# P5d_Filter2B.net
KiCad netlist of a schematic drawn in Altium Designer
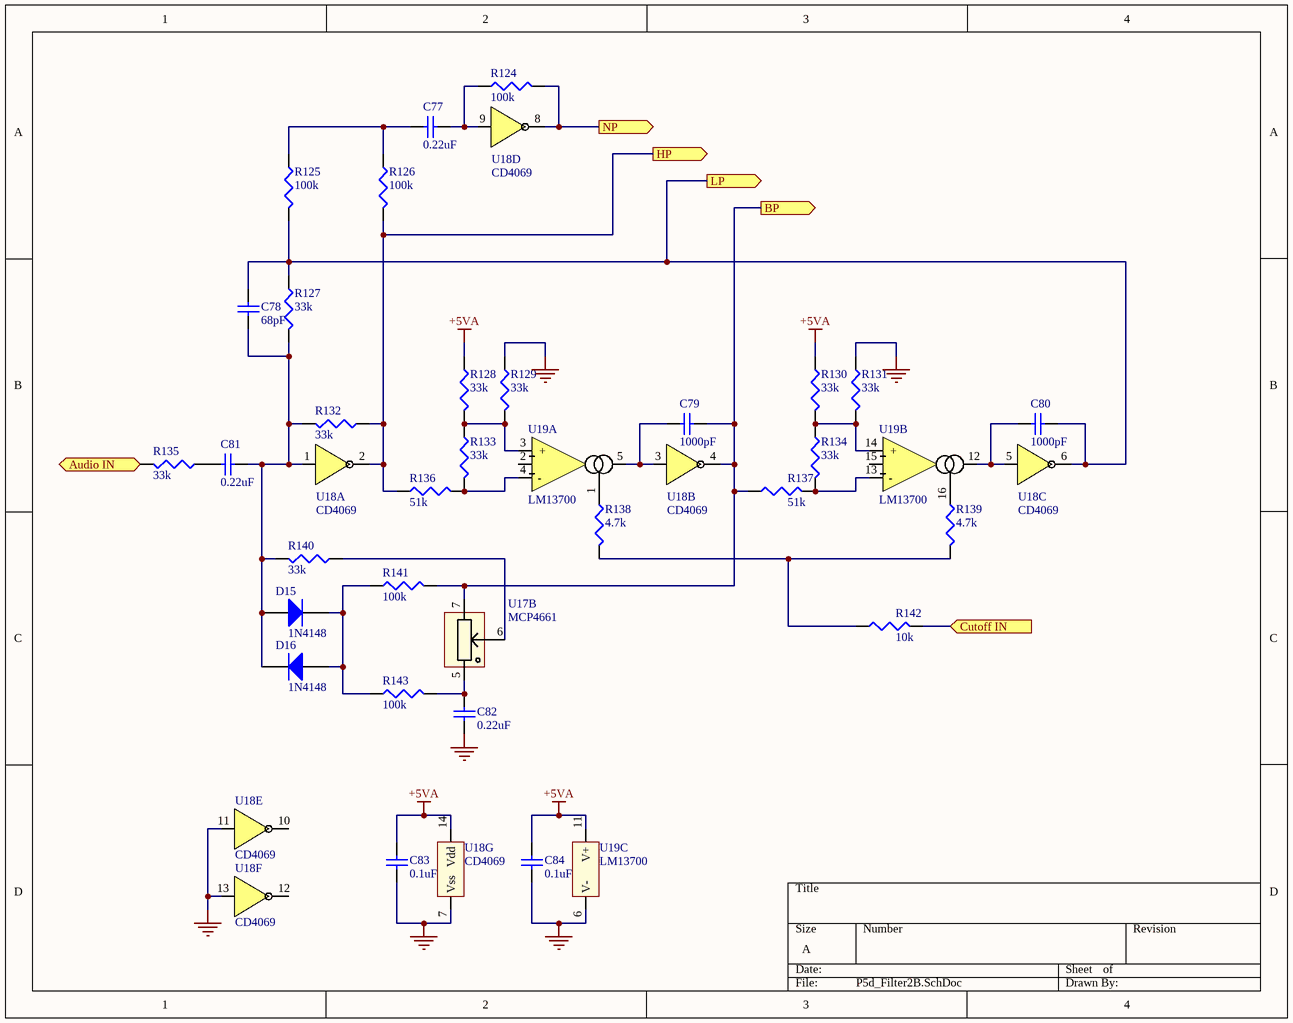
[diagram p0: P5d_Filter2B.SchDoc]

(export (version "E")
  (design (tool "Eeschema 10.0.6"))
  (components
    (comp (ref "C77")
      (value "0.22uF")
      (footprint "CAP 0603 (1608 metric)")
      (description "Capacitor (Semiconductor SIM Model)")
      (libsource (lib "Miscellaneous Devices") (part "Cap Semi"))
    )
    (comp (ref "C78")
      (value "68pF")
      (footprint "CAP 0603 (1608 metric)")
      (description "Capacitor (Semiconductor SIM Model)")
      (libsource (lib "Miscellaneous Devices") (part "Cap Semi"))
    )
    (comp (ref "C79")
      (value "1000pF")
      (footprint "CAP 0603 (1608 metric)")
      (description "Capacitor (Semiconductor SIM Model)")
      (libsource (lib "Miscellaneous Devices") (part "Cap Semi"))
    )
    (comp (ref "C80")
      (value "1000pF")
      (footprint "CAP 0603 (1608 metric)")
      (description "Capacitor (Semiconductor SIM Model)")
      (libsource (lib "Miscellaneous Devices") (part "Cap Semi"))
    )
    (comp (ref "C81")
      (value "0.22uF")
      (footprint "CAP 0603 (1608 metric)")
      (description "Capacitor (Semiconductor SIM Model)")
      (libsource (lib "Miscellaneous Devices") (part "Cap Semi"))
    )
    (comp (ref "C82")
      (value "0.22uF")
      (footprint "CAP 0603 (1608 metric)")
      (description "Capacitor (Semiconductor SIM Model)")
      (libsource (lib "Miscellaneous Devices") (part "Cap Semi"))
    )
    (comp (ref "C83")
      (value "0.1uF")
      (footprint "CAP 0603 (1608 metric)")
      (description "Capacitor (Semiconductor SIM Model)")
      (libsource (lib "Miscellaneous Devices") (part "Cap Semi"))
    )
    (comp (ref "C84")
      (value "0.1uF")
      (footprint "CAP 0603 (1608 metric)")
      (description "Capacitor (Semiconductor SIM Model)")
      (libsource (lib "Miscellaneous Devices") (part "Cap Semi"))
    )
    (comp (ref "D15")
      (value "1N4148")
      (description "High Conductance Fast Diode")
      (libsource (lib "Miscellaneous Devices") (part "Diode 1N4148"))
    )
    (comp (ref "D16")
      (value "1N4148")
      (description "High Conductance Fast Diode")
      (libsource (lib "Miscellaneous Devices") (part "Diode 1N4148"))
    )
    (comp (ref "R124")
      (value "100k")
      (footprint "RES 0603 (1608 metric)")
      (description "Resistor")
      (libsource (lib "Miscellaneous Devices") (part "Res3"))
    )
    (comp (ref "R125")
      (value "100k")
      (footprint "RES 0603 (1608 metric)")
      (description "Resistor")
      (libsource (lib "Miscellaneous Devices") (part "Res3"))
    )
    (comp (ref "R126")
      (value "100k")
      (footprint "RES 0603 (1608 metric)")
      (description "Resistor")
      (libsource (lib "Miscellaneous Devices") (part "Res3"))
    )
    (comp (ref "R127")
      (value "33k")
      (footprint "RES 0603 (1608 metric)")
      (description "Resistor")
      (libsource (lib "Miscellaneous Devices") (part "Res3"))
    )
    (comp (ref "R128")
      (value "33k")
      (footprint "RES 0603 (1608 metric)")
      (description "Resistor")
      (libsource (lib "Miscellaneous Devices") (part "Res3"))
    )
    (comp (ref "R129")
      (value "33k")
      (footprint "RES 0603 (1608 metric)")
      (description "Resistor")
      (libsource (lib "Miscellaneous Devices") (part "Res3"))
    )
    (comp (ref "R130")
      (value "33k")
      (footprint "RES 0603 (1608 metric)")
      (description "Resistor")
      (libsource (lib "Miscellaneous Devices") (part "Res3"))
    )
    (comp (ref "R131")
      (value "33k")
      (footprint "RES 0603 (1608 metric)")
      (description "Resistor")
      (libsource (lib "Miscellaneous Devices") (part "Res3"))
    )
    (comp (ref "R132")
      (value "33k")
      (footprint "RES 0603 (1608 metric)")
      (description "Resistor")
      (libsource (lib "Miscellaneous Devices") (part "Res3"))
    )
    (comp (ref "R133")
      (value "33k")
      (footprint "RES 0603 (1608 metric)")
      (description "Resistor")
      (libsource (lib "Miscellaneous Devices") (part "Res3"))
    )
    (comp (ref "R134")
      (value "33k")
      (footprint "RES 0603 (1608 metric)")
      (description "Resistor")
      (libsource (lib "Miscellaneous Devices") (part "Res3"))
    )
    (comp (ref "R135")
      (value "33k")
      (footprint "RES 0603 (1608 metric)")
      (description "Resistor")
      (libsource (lib "Miscellaneous Devices") (part "Res3"))
    )
    (comp (ref "R136")
      (value "51k")
      (footprint "RES 0603 (1608 metric)")
      (description "Resistor")
      (libsource (lib "Miscellaneous Devices") (part "Res3"))
    )
    (comp (ref "R137")
      (value "51k")
      (footprint "RES 0603 (1608 metric)")
      (description "Resistor")
      (libsource (lib "Miscellaneous Devices") (part "Res3"))
    )
    (comp (ref "R138")
      (value "4.7k")
      (footprint "RES 0603 (1608 metric)")
      (description "Resistor")
      (libsource (lib "Miscellaneous Devices") (part "Res3"))
    )
    (comp (ref "R139")
      (value "4.7k")
      (footprint "RES 0603 (1608 metric)")
      (description "Resistor")
      (libsource (lib "Miscellaneous Devices") (part "Res3"))
    )
    (comp (ref "R140")
      (value "33k")
      (footprint "RES 0603 (1608 metric)")
      (description "Resistor")
      (libsource (lib "Miscellaneous Devices") (part "Res3"))
    )
    (comp (ref "R141")
      (value "100k")
      (footprint "RES 0603 (1608 metric)")
      (description "Resistor")
      (libsource (lib "Miscellaneous Devices") (part "Res3"))
    )
    (comp (ref "R142")
      (value "10k")
      (footprint "RES 0603 (1608 metric)")
      (description "Resistor")
      (libsource (lib "Miscellaneous Devices") (part "Res3"))
    )
    (comp (ref "R143")
      (value "100k")
      (footprint "RES 0603 (1608 metric)")
      (description "Resistor")
      (libsource (lib "Miscellaneous Devices") (part "Res3"))
    )
    (comp (ref "U17")
      (value "MCP4661")
      (description "Dual DigiPot non volatile I2C")
      (libsource (lib "FilterPoC") (part "MCP4661"))
    )
    (comp (ref "U18")
      (value "CD4069")
      (description "Hex Inverter")
      (libsource (lib "FilterPoC") (part "CD4069"))
    )
    (comp (ref "U19")
      (value "LM13700")
      (description "Dual Transconductance OpAmp")
      (libsource (lib "") (part "LM13700M_1"))
    )
  )
  (nets
    (net (code "1") (name "+5VA") (class "Default")
      (node (ref "C83") (pin "1") (pinfunction "1_1") (pintype "passive"))
      (node (ref "C84") (pin "1") (pinfunction "1_1") (pintype "passive"))
      (node (ref "R128") (pin "1") (pinfunction "1_1") (pintype "passive"))
      (node (ref "R130") (pin "1") (pinfunction "1_1") (pintype "passive"))
      (node (ref "U18") (pin "14") (pinfunction "Vdd_14") (pintype "power_in"))
      (node (ref "U19") (pin "11") (pinfunction "V+_11") (pintype "power_in"))
    )
    (net (code "2") (name "/Audio IN") (class "Default")
      (node (ref "R135") (pin "2") (pinfunction "2_2") (pintype "passive"))
    )
    (net (code "3") (name "/BP") (class "Default")
      (node (ref "C79") (pin "2") (pinfunction "2_2") (pintype "passive"))
      (node (ref "R137") (pin "1") (pinfunction "1_1") (pintype "passive"))
      (node (ref "R141") (pin "2") (pinfunction "2_2") (pintype "passive"))
      (node (ref "U17") (pin "7") (pinfunction "P1A_7") (pintype "passive"))
      (node (ref "U18") (pin "4") (pinfunction "~{B}_4") (pintype "passive"))
    )
    (net (code "4") (name "/Cutoff IN") (class "Default")
      (node (ref "R142") (pin "2") (pinfunction "2_2") (pintype "passive"))
    )
    (net (code "5") (name "/HP") (class "Default")
      (node (ref "R126") (pin "2") (pinfunction "2_2") (pintype "passive"))
      (node (ref "R132") (pin "1") (pinfunction "1_1") (pintype "passive"))
      (node (ref "R136") (pin "1") (pinfunction "1_1") (pintype "passive"))
      (node (ref "U18") (pin "2") (pinfunction "~{A}_2") (pintype "passive"))
    )
    (net (code "6") (name "/LP") (class "Default")
      (node (ref "C78") (pin "2") (pinfunction "2_2") (pintype "passive"))
      (node (ref "C80") (pin "2") (pinfunction "2_2") (pintype "passive"))
      (node (ref "R125") (pin "2") (pinfunction "2_2") (pintype "passive"))
      (node (ref "R127") (pin "1") (pinfunction "1_1") (pintype "passive"))
      (node (ref "U18") (pin "6") (pinfunction "~{C}_6") (pintype "passive"))
    )
    (net (code "7") (name "/NP") (class "Default")
      (node (ref "R124") (pin "2") (pinfunction "2_2") (pintype "passive"))
      (node (ref "U18") (pin "8") (pinfunction "~{D}_8") (pintype "passive"))
    )
    (net (code "8") (name "GND") (class "Default")
      (node (ref "C82") (pin "2") (pinfunction "2_2") (pintype "passive"))
      (node (ref "C83") (pin "2") (pinfunction "2_2") (pintype "passive"))
      (node (ref "C84") (pin "2") (pinfunction "2_2") (pintype "passive"))
      (node (ref "R129") (pin "1") (pinfunction "1_1") (pintype "passive"))
      (node (ref "R131") (pin "1") (pinfunction "1_1") (pintype "passive"))
      (node (ref "U18") (pin "11") (pinfunction "E_11") (pintype "passive"))
      (node (ref "U18") (pin "13") (pinfunction "F_13") (pintype "passive"))
      (node (ref "U18") (pin "7") (pinfunction "Vss_7") (pintype "power_in"))
      (node (ref "U19") (pin "6") (pinfunction "V-_6") (pintype "power_in"))
    )
    (net (code "9") (name "Net-(C77-Pad1)") (class "Default")
      (node (ref "C77") (pin "1") (pinfunction "1_1") (pintype "passive"))
      (node (ref "R125") (pin "1") (pinfunction "1_1") (pintype "passive"))
      (node (ref "R126") (pin "1") (pinfunction "1_1") (pintype "passive"))
    )
    (net (code "10") (name "Net-(C81-Pad1)") (class "Default")
      (node (ref "C81") (pin "1") (pinfunction "1_1") (pintype "passive"))
      (node (ref "R135") (pin "1") (pinfunction "1_1") (pintype "passive"))
    )
    (net (code "11") (name "Net-(D15-A)") (class "Default")
      (node (ref "C78") (pin "1") (pinfunction "1_1") (pintype "passive"))
      (node (ref "C81") (pin "2") (pinfunction "2_2") (pintype "passive"))
      (node (ref "D15") (pin "1") (pinfunction "A_1") (pintype "passive"))
      (node (ref "D16") (pin "2") (pinfunction "K_2") (pintype "passive"))
      (node (ref "R127") (pin "2") (pinfunction "2_2") (pintype "passive"))
      (node (ref "R132") (pin "2") (pinfunction "2_2") (pintype "passive"))
      (node (ref "R140") (pin "2") (pinfunction "2_2") (pintype "passive"))
      (node (ref "U18") (pin "1") (pinfunction "A_1") (pintype "passive"))
    )
    (net (code "12") (name "Net-(D15-K)") (class "Default")
      (node (ref "D15") (pin "2") (pinfunction "K_2") (pintype "passive"))
      (node (ref "D16") (pin "1") (pinfunction "A_1") (pintype "passive"))
      (node (ref "R141") (pin "1") (pinfunction "1_1") (pintype "passive"))
      (node (ref "R143") (pin "1") (pinfunction "1_1") (pintype "passive"))
    )
    (net (code "13") (name "Net-(R138-Pad2)") (class "Default")
      (node (ref "R138") (pin "2") (pinfunction "2_2") (pintype "passive"))
      (node (ref "R139") (pin "2") (pinfunction "2_2") (pintype "passive"))
      (node (ref "R142") (pin "1") (pinfunction "1_1") (pintype "passive"))
    )
    (net (code "14") (name "Net-(U17B-P1B)") (class "Default")
      (node (ref "C82") (pin "1") (pinfunction "1_1") (pintype "passive"))
      (node (ref "R143") (pin "2") (pinfunction "2_2") (pintype "passive"))
      (node (ref "U17") (pin "5") (pinfunction "P1B_5") (pintype "passive"))
    )
    (net (code "15") (name "Net-(U17B-P1W)") (class "Default")
      (node (ref "R140") (pin "1") (pinfunction "1_1") (pintype "passive"))
      (node (ref "U17") (pin "6") (pinfunction "P1W_6") (pintype "passive"))
    )
    (net (code "16") (name "Net-(U18B-B)") (class "Default")
      (node (ref "C79") (pin "1") (pinfunction "1_1") (pintype "passive"))
      (node (ref "U18") (pin "3") (pinfunction "B_3") (pintype "passive"))
      (node (ref "U19") (pin "5") (pinfunction "OUT_5") (pintype "passive"))
    )
    (net (code "17") (name "Net-(U18C-C)") (class "Default")
      (node (ref "C80") (pin "1") (pinfunction "1_1") (pintype "passive"))
      (node (ref "U18") (pin "5") (pinfunction "C_5") (pintype "passive"))
      (node (ref "U19") (pin "12") (pinfunction "OUT_12") (pintype "passive"))
    )
    (net (code "18") (name "Net-(U18D-D)") (class "Default")
      (node (ref "C77") (pin "2") (pinfunction "2_2") (pintype "passive"))
      (node (ref "R124") (pin "1") (pinfunction "1_1") (pintype "passive"))
      (node (ref "U18") (pin "9") (pinfunction "D_9") (pintype "passive"))
    )
    (net (code "19") (name "Net-(U19A-+)") (class "Default")
      (node (ref "R128") (pin "2") (pinfunction "2_2") (pintype "passive"))
      (node (ref "R129") (pin "2") (pinfunction "2_2") (pintype "passive"))
      (node (ref "R133") (pin "1") (pinfunction "1_1") (pintype "passive"))
      (node (ref "U19") (pin "3") (pinfunction "+_3") (pintype "passive"))
    )
    (net (code "20") (name "Net-(U19A--)") (class "Default")
      (node (ref "R133") (pin "2") (pinfunction "2_2") (pintype "passive"))
      (node (ref "R136") (pin "2") (pinfunction "2_2") (pintype "passive"))
      (node (ref "U19") (pin "4") (pinfunction "-_4") (pintype "passive"))
    )
    (net (code "21") (name "Net-(U19A-BIAS)") (class "Default")
      (node (ref "R138") (pin "1") (pinfunction "1_1") (pintype "passive"))
      (node (ref "U19") (pin "1") (pinfunction "BIAS_1") (pintype "passive"))
    )
    (net (code "22") (name "Net-(U19B-+)") (class "Default")
      (node (ref "R130") (pin "2") (pinfunction "2_2") (pintype "passive"))
      (node (ref "R131") (pin "2") (pinfunction "2_2") (pintype "passive"))
      (node (ref "R134") (pin "1") (pinfunction "1_1") (pintype "passive"))
      (node (ref "U19") (pin "14") (pinfunction "+_14") (pintype "passive"))
    )
    (net (code "23") (name "Net-(U19B--)") (class "Default")
      (node (ref "R134") (pin "2") (pinfunction "2_2") (pintype "passive"))
      (node (ref "R137") (pin "2") (pinfunction "2_2") (pintype "passive"))
      (node (ref "U19") (pin "13") (pinfunction "-_13") (pintype "passive"))
    )
    (net (code "24") (name "Net-(U19B-BIAS)") (class "Default")
      (node (ref "R139") (pin "1") (pinfunction "1_1") (pintype "passive"))
      (node (ref "U19") (pin "16") (pinfunction "BIAS_16") (pintype "passive"))
    )
    (net (code "25") (name "unconnected-(U18E-~{E}-Pad10)") (class "Default")
      (node (ref "U18") (pin "10") (pinfunction "~{E}_10") (pintype "passive"))
    )
    (net (code "26") (name "unconnected-(U18F-~{F}-Pad12)") (class "Default")
      (node (ref "U18") (pin "12") (pinfunction "~{F}_12") (pintype "passive"))
    )
    (net (code "27") (name "unconnected-(U19A-Diode_BIAS-Pad2)") (class "Default")
      (node (ref "U19") (pin "2") (pinfunction "Diode_BIAS_2") (pintype "passive"))
    )
    (net (code "28") (name "unconnected-(U19B-Diode_BIAS-Pad15)") (class "Default")
      (node (ref "U19") (pin "15") (pinfunction "Diode_BIAS_15") (pintype "passive"))
    )
  )
)
